# JW24A10L_revE.net
KiCad netlist of a schematic drawn in EAGLE
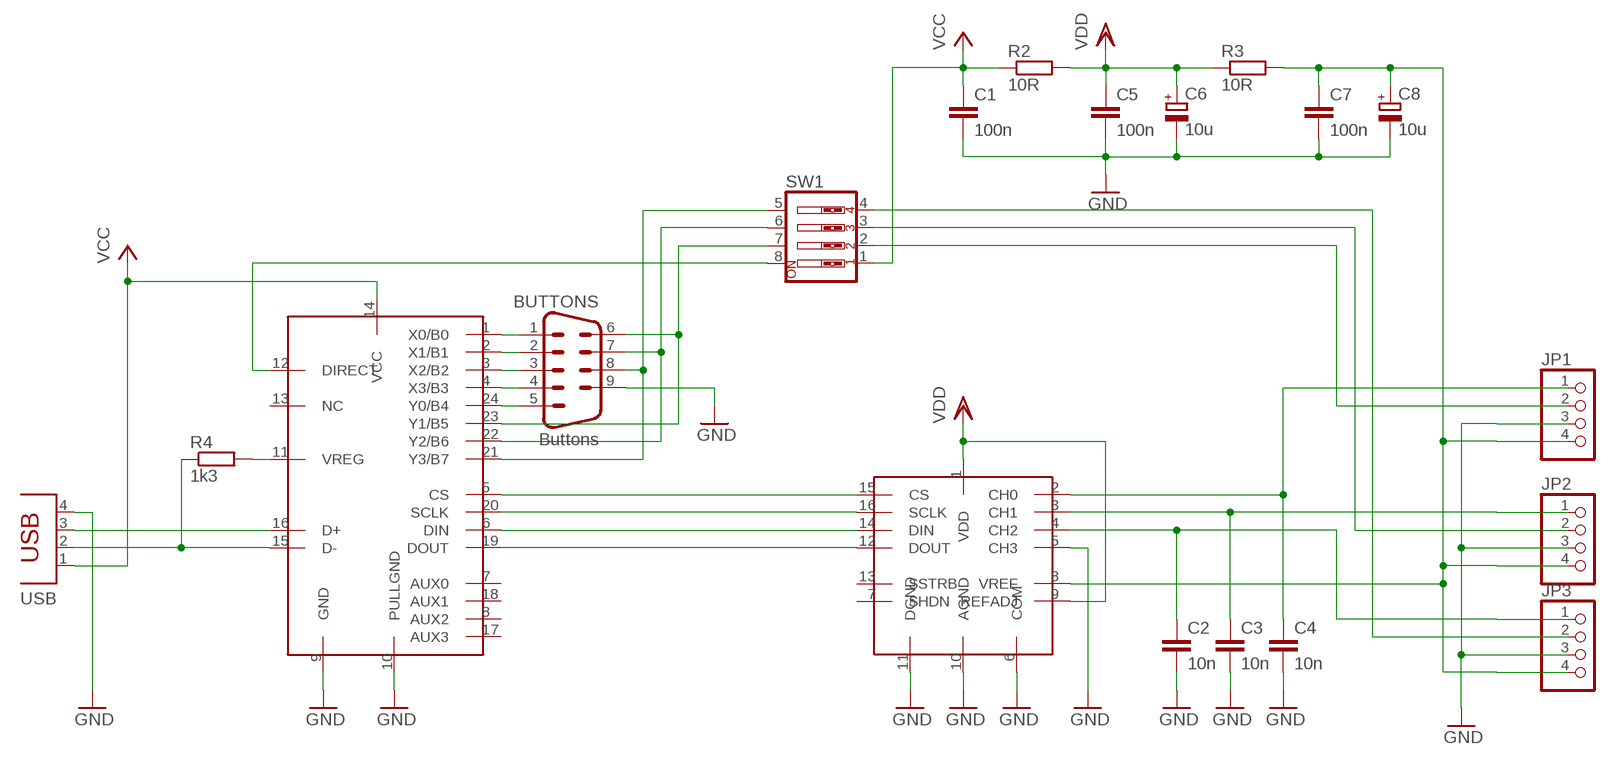
[diagram p0: schematic, sheet 1]

(export (version "E")
  (design (tool "Eeschema 10.0.6"))
  (components
    (comp (ref "BUTTONS")
      (value "Buttons")
      (footprint "eagle-import:M09H")
      (libsource (lib "eagle-import") (part "M09H"))
    )
    (comp (ref "C1")
      (value "100n")
      (footprint "eagle-import:C025-025X050")
      (libsource (lib "eagle-import") (part "C-EU025-025X050"))
    )
    (comp (ref "C2")
      (value "10n")
      (footprint "eagle-import:C025-025X050")
      (libsource (lib "eagle-import") (part "C-EU025-025X050"))
    )
    (comp (ref "C3")
      (value "10n")
      (footprint "eagle-import:C025-025X050")
      (libsource (lib "eagle-import") (part "C-EU025-025X050"))
    )
    (comp (ref "C4")
      (value "10n")
      (footprint "eagle-import:C025-025X050")
      (libsource (lib "eagle-import") (part "C-EU025-025X050"))
    )
    (comp (ref "C5")
      (value "100n")
      (footprint "eagle-import:C025-025X050")
      (libsource (lib "eagle-import") (part "C-EU025-025X050"))
    )
    (comp (ref "C6")
      (value "10u")
      (footprint "eagle-import:E2-5")
      (libsource (lib "eagle-import") (part "CPOL-EUE2-5"))
    )
    (comp (ref "C7")
      (value "100n")
      (footprint "eagle-import:C025-025X050")
      (libsource (lib "eagle-import") (part "C-EU025-025X050"))
    )
    (comp (ref "C8")
      (value "10u")
      (footprint "eagle-import:E2-5")
      (libsource (lib "eagle-import") (part "CPOL-EUE2-5"))
    )
    (comp (ref "JP1")
      (value "PINHD-1X4")
      (footprint "eagle-import:1X04")
      (libsource (lib "eagle-import") (part "PINHD-1X4"))
    )
    (comp (ref "JP2")
      (value "PINHD-1X4")
      (footprint "eagle-import:1X04")
      (libsource (lib "eagle-import") (part "PINHD-1X4"))
    )
    (comp (ref "JP3")
      (value "PINHD-1X4")
      (footprint "eagle-import:1X04")
      (libsource (lib "eagle-import") (part "PINHD-1X4"))
    )
    (comp (ref "R2")
      (value "10R")
      (footprint "eagle-import:0207_2V")
      (libsource (lib "eagle-import") (part "R-EU_0207/2V"))
    )
    (comp (ref "R3")
      (value "10R")
      (footprint "eagle-import:0207_2V")
      (libsource (lib "eagle-import") (part "R-EU_0207/2V"))
    )
    (comp (ref "R4")
      (value "1k3")
      (footprint "eagle-import:0207_2V")
      (libsource (lib "eagle-import") (part "R-EU_0207/2V"))
    )
    (comp (ref "SW1")
      (value "SW_DIP-4")
      (footprint "eagle-import:EDG-04")
      (libsource (lib "eagle-import") (part "SW_DIP-4"))
    )
    (comp (ref "U$1")
      (value "MAX1249")
      (footprint "eagle-import:DIL16")
      (libsource (lib "eagle-import") (part "MAX1249"))
    )
    (comp (ref "U$2")
      (value "JW24A10L")
      (footprint "eagle-import:DIL24-3")
      (libsource (lib "eagle-import") (part "JW24A10L"))
    )
    (comp (ref "USB")
      (value "PN61729")
      (footprint "eagle-import:PN61729")
      (libsource (lib "eagle-import") (part "PN61729"))
    )
  )
  (nets
    (net (code "1") (name "/AUX0") (class "Default")
      (node (ref "U$2") (pin "7") (pinfunction "AUX0_7") (pintype "power_in"))
    )
    (net (code "2") (name "/AUX1") (class "Default")
      (node (ref "U$2") (pin "18") (pinfunction "AUX1_18") (pintype "power_in"))
    )
    (net (code "3") (name "/AUX2") (class "Default")
      (node (ref "U$2") (pin "8") (pinfunction "AUX2_8") (pintype "power_in"))
    )
    (net (code "4") (name "/AUX3") (class "Default")
      (node (ref "U$2") (pin "17") (pinfunction "AUX3_17") (pintype "power_in"))
    )
    (net (code "5") (name "GND") (class "Default")
      (node (ref "BUTTONS") (pin "9") (pinfunction "9_9") (pintype "passive"))
      (node (ref "C1") (pin "2") (pinfunction "2_2") (pintype "passive"))
      (node (ref "C2") (pin "2") (pinfunction "2_2") (pintype "passive"))
      (node (ref "C3") (pin "2") (pinfunction "2_2") (pintype "passive"))
      (node (ref "C4") (pin "2") (pinfunction "2_2") (pintype "passive"))
      (node (ref "C5") (pin "2") (pinfunction "2_2") (pintype "passive"))
      (node (ref "C6") (pin "-") (pinfunction "-_-") (pintype "passive"))
      (node (ref "C7") (pin "2") (pinfunction "2_2") (pintype "passive"))
      (node (ref "C8") (pin "-") (pinfunction "-_-") (pintype "passive"))
      (node (ref "JP1") (pin "3") (pinfunction "3_3") (pintype "passive"))
      (node (ref "JP2") (pin "3") (pinfunction "3_3") (pintype "passive"))
      (node (ref "JP3") (pin "3") (pinfunction "3_3") (pintype "passive"))
      (node (ref "U$1") (pin "10") (pinfunction "AGND_10") (pintype "power_in"))
      (node (ref "U$1") (pin "11") (pinfunction "DGND_11") (pintype "power_in"))
      (node (ref "U$1") (pin "5") (pinfunction "CH3_5") (pintype "input"))
      (node (ref "U$1") (pin "6") (pinfunction "COM_6") (pintype "bidirectional"))
      (node (ref "U$2") (pin "10") (pinfunction "PULLGND_10") (pintype "power_in"))
      (node (ref "U$2") (pin "9") (pinfunction "GND_9") (pintype "power_in"))
      (node (ref "USB") (pin "4") (pinfunction "4_4") (pintype "passive"))
    )
    (net (code "6") (name "Net-(JP1-Pad2)") (class "Default")
      (node (ref "JP1") (pin "2") (pinfunction "2_2") (pintype "passive"))
      (node (ref "SW1") (pin "2") (pinfunction "2_2") (pintype "passive"))
    )
    (net (code "7") (name "Net-(JP2-Pad2)") (class "Default")
      (node (ref "JP2") (pin "2") (pinfunction "2_2") (pintype "passive"))
      (node (ref "SW1") (pin "3") (pinfunction "3_3") (pintype "passive"))
    )
    (net (code "8") (name "Net-(JP3-Pad2)") (class "Default")
      (node (ref "JP3") (pin "2") (pinfunction "2_2") (pintype "passive"))
      (node (ref "SW1") (pin "4") (pinfunction "4_4") (pintype "passive"))
    )
    (net (code "9") (name "Net-(U$1-CH0)") (class "Default")
      (node (ref "C4") (pin "1") (pinfunction "1_1") (pintype "passive"))
      (node (ref "JP1") (pin "1") (pinfunction "1_1") (pintype "passive"))
      (node (ref "U$1") (pin "2") (pinfunction "CH0_2") (pintype "input"))
    )
    (net (code "10") (name "Net-(U$1-CH1)") (class "Default")
      (node (ref "C3") (pin "1") (pinfunction "1_1") (pintype "passive"))
      (node (ref "JP2") (pin "1") (pinfunction "1_1") (pintype "passive"))
      (node (ref "U$1") (pin "3") (pinfunction "CH1_3") (pintype "input"))
    )
    (net (code "11") (name "Net-(U$1-CH2)") (class "Default")
      (node (ref "C2") (pin "1") (pinfunction "1_1") (pintype "passive"))
      (node (ref "JP3") (pin "1") (pinfunction "1_1") (pintype "passive"))
      (node (ref "U$1") (pin "4") (pinfunction "CH2_4") (pintype "input"))
    )
    (net (code "12") (name "Net-(U$1-CS)") (class "Default")
      (node (ref "U$1") (pin "15") (pinfunction "CS_15") (pintype "bidirectional"))
      (node (ref "U$2") (pin "5") (pinfunction "CS_5") (pintype "bidirectional"))
    )
    (net (code "13") (name "Net-(U$1-DIN)") (class "Default")
      (node (ref "U$1") (pin "14") (pinfunction "DIN_14") (pintype "bidirectional"))
      (node (ref "U$2") (pin "6") (pinfunction "DIN_6") (pintype "bidirectional"))
    )
    (net (code "14") (name "Net-(U$1-DOUT)") (class "Default")
      (node (ref "U$1") (pin "12") (pinfunction "DOUT_12") (pintype "bidirectional"))
      (node (ref "U$2") (pin "19") (pinfunction "DOUT_19") (pintype "bidirectional"))
    )
    (net (code "15") (name "Net-(U$1-SCLK)") (class "Default")
      (node (ref "U$1") (pin "16") (pinfunction "SCLK_16") (pintype "bidirectional"))
      (node (ref "U$2") (pin "20") (pinfunction "SCLK_20") (pintype "bidirectional"))
    )
    (net (code "16") (name "Net-(U$1-VREF)") (class "Default")
      (node (ref "C7") (pin "1") (pinfunction "1_1") (pintype "passive"))
      (node (ref "C8") (pin "+") (pinfunction "+_+") (pintype "passive"))
      (node (ref "JP1") (pin "4") (pinfunction "4_4") (pintype "passive"))
      (node (ref "JP2") (pin "4") (pinfunction "4_4") (pintype "passive"))
      (node (ref "JP3") (pin "4") (pinfunction "4_4") (pintype "passive"))
      (node (ref "R3") (pin "2") (pinfunction "2_2") (pintype "passive"))
      (node (ref "U$1") (pin "8") (pinfunction "VREF_8") (pintype "bidirectional"))
    )
    (net (code "17") (name "Net-(U$2-D+)") (class "Default")
      (node (ref "U$2") (pin "16") (pinfunction "D+_16") (pintype "bidirectional"))
      (node (ref "USB") (pin "3") (pinfunction "3_3") (pintype "passive"))
    )
    (net (code "18") (name "Net-(U$2-D-)") (class "Default")
      (node (ref "R4") (pin "1") (pinfunction "1_1") (pintype "passive"))
      (node (ref "U$2") (pin "15") (pinfunction "D-_15") (pintype "bidirectional"))
      (node (ref "USB") (pin "2") (pinfunction "2_2") (pintype "passive"))
    )
    (net (code "19") (name "Net-(U$2-DIRECT)") (class "Default")
      (node (ref "SW1") (pin "8") (pinfunction "8_8") (pintype "passive"))
      (node (ref "U$2") (pin "12") (pinfunction "DIRECT_12") (pintype "bidirectional"))
    )
    (net (code "20") (name "Net-(U$2-VREG)") (class "Default")
      (node (ref "R4") (pin "2") (pinfunction "2_2") (pintype "passive"))
      (node (ref "U$2") (pin "11") (pinfunction "VREG_11") (pintype "bidirectional"))
    )
    (net (code "21") (name "Net-(U$2-X0{slash}B0)") (class "Default")
      (node (ref "BUTTONS") (pin "1") (pinfunction "1_1") (pintype "passive"))
      (node (ref "U$2") (pin "1") (pinfunction "X0/B0_1") (pintype "bidirectional"))
    )
    (net (code "22") (name "Net-(U$2-X1{slash}B1)") (class "Default")
      (node (ref "BUTTONS") (pin "2") (pinfunction "2_2") (pintype "passive"))
      (node (ref "U$2") (pin "2") (pinfunction "X1/B1_2") (pintype "bidirectional"))
    )
    (net (code "23") (name "Net-(U$2-X2{slash}B2)") (class "Default")
      (node (ref "BUTTONS") (pin "3") (pinfunction "3_3") (pintype "passive"))
      (node (ref "U$2") (pin "3") (pinfunction "X2/B2_3") (pintype "bidirectional"))
    )
    (net (code "24") (name "Net-(U$2-X3{slash}B3)") (class "Default")
      (node (ref "BUTTONS") (pin "4") (pinfunction "4_4") (pintype "passive"))
      (node (ref "U$2") (pin "4") (pinfunction "X3/B3_4") (pintype "bidirectional"))
    )
    (net (code "25") (name "Net-(U$2-Y0{slash}B4)") (class "Default")
      (node (ref "BUTTONS") (pin "5") (pinfunction "5_5") (pintype "passive"))
      (node (ref "U$2") (pin "24") (pinfunction "Y0/B4_24") (pintype "bidirectional"))
    )
    (net (code "26") (name "Net-(U$2-Y1{slash}B5)") (class "Default")
      (node (ref "BUTTONS") (pin "6") (pinfunction "6_6") (pintype "passive"))
      (node (ref "SW1") (pin "7") (pinfunction "7_7") (pintype "passive"))
      (node (ref "U$2") (pin "23") (pinfunction "Y1/B5_23") (pintype "bidirectional"))
    )
    (net (code "27") (name "Net-(U$2-Y2{slash}B6)") (class "Default")
      (node (ref "BUTTONS") (pin "7") (pinfunction "7_7") (pintype "passive"))
      (node (ref "SW1") (pin "6") (pinfunction "6_6") (pintype "passive"))
      (node (ref "U$2") (pin "22") (pinfunction "Y2/B6_22") (pintype "bidirectional"))
    )
    (net (code "28") (name "Net-(U$2-Y3{slash}B7)") (class "Default")
      (node (ref "BUTTONS") (pin "8") (pinfunction "8_8") (pintype "passive"))
      (node (ref "SW1") (pin "5") (pinfunction "5_5") (pintype "passive"))
      (node (ref "U$2") (pin "21") (pinfunction "Y3/B7_21") (pintype "bidirectional"))
    )
    (net (code "29") (name "VCC") (class "Default")
      (node (ref "C1") (pin "1") (pinfunction "1_1") (pintype "passive"))
      (node (ref "R2") (pin "1") (pinfunction "1_1") (pintype "passive"))
      (node (ref "SW1") (pin "1") (pinfunction "1_1") (pintype "passive"))
      (node (ref "U$2") (pin "14") (pinfunction "VCC_14") (pintype "power_in"))
      (node (ref "USB") (pin "1") (pinfunction "1_1") (pintype "passive"))
    )
    (net (code "30") (name "VDD") (class "Default")
      (node (ref "C5") (pin "1") (pinfunction "1_1") (pintype "passive"))
      (node (ref "C6") (pin "+") (pinfunction "+_+") (pintype "passive"))
      (node (ref "R2") (pin "2") (pinfunction "2_2") (pintype "passive"))
      (node (ref "R3") (pin "1") (pinfunction "1_1") (pintype "passive"))
      (node (ref "U$1") (pin "1") (pinfunction "VDD_1") (pintype "power_in"))
      (node (ref "U$1") (pin "9") (pinfunction "REFADJ_9") (pintype "bidirectional"))
    )
    (net (code "31") (name "unconnected-(U$1-SHDN-Pad7)") (class "Default")
      (node (ref "U$1") (pin "7") (pinfunction "SHDN_7") (pintype "bidirectional"))
    )
    (net (code "32") (name "unconnected-(U$1-SSTRB-Pad13)") (class "Default")
      (node (ref "U$1") (pin "13") (pinfunction "SSTRB_13") (pintype "bidirectional"))
    )
    (net (code "33") (name "unconnected-(U$2-NC-Pad13)") (class "Default")
      (node (ref "U$2") (pin "13") (pinfunction "NC_13") (pintype "bidirectional"))
    )
  )
)
